# gumstix_expansion_board.net
KiCad netlist of a schematic drawn in Altium Designer
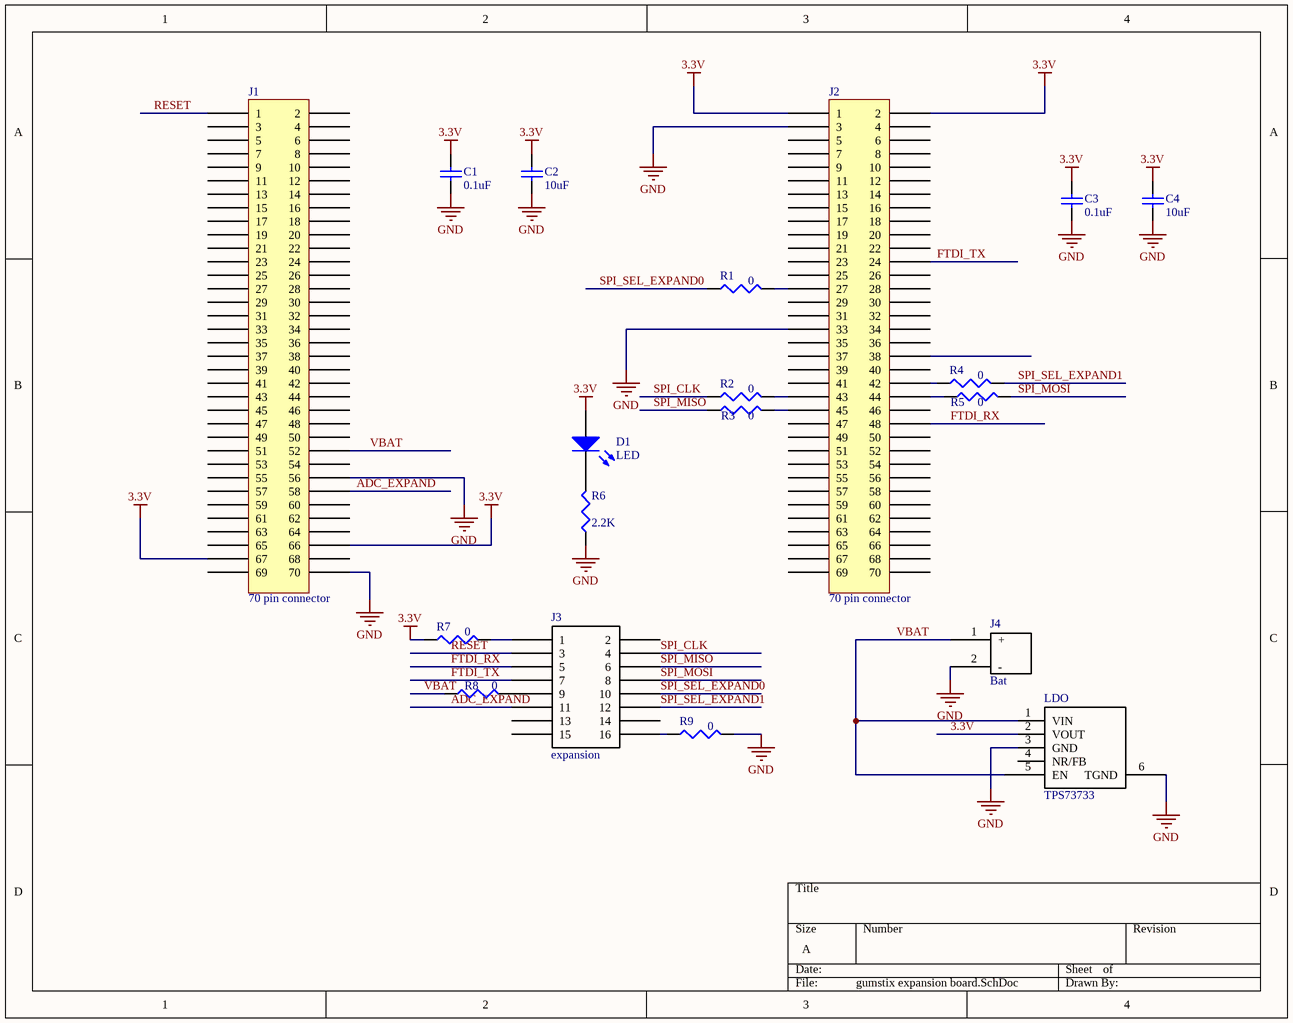
[diagram p0: gumstix expansion board.SchDoc]

(export (version "E")
  (design (tool "Eeschema 10.0.6"))
  (components
    (comp (ref "C1")
      (value "0.1uF")
      (footprint "CAPC1005L")
      (description "Capacitor")
      (fields (field (name "PUBLISHER") "Altium Limited"))
      (libsource (lib "Miscellaneous Devices") (part "Cap"))
    )
    (comp (ref "C2")
      (value "10uF")
      (footprint "CAPC1608L")
      (description "Capacitor (Semiconductor SIM Model)")
      (fields (field (name "Comment") "Cap Semi") (field (name "PUBLISHER") "Altium Limited"))
      (libsource (lib "Miscellaneous Devices") (part "Cap Semi"))
    )
    (comp (ref "C3")
      (value "0.1uF")
      (footprint "CAPC1005L")
      (description "Capacitor")
      (fields (field (name "PUBLISHER") "Altium Limited"))
      (libsource (lib "Miscellaneous Devices") (part "Cap"))
    )
    (comp (ref "C4")
      (value "10uF")
      (footprint "CAPC1608L")
      (description "Capacitor (Semiconductor SIM Model)")
      (fields (field (name "Comment") "Cap Semi") (field (name "PUBLISHER") "Altium Limited"))
      (libsource (lib "Miscellaneous Devices") (part "Cap Semi"))
    )
    (comp (ref "D1") (value "LED") (footprint "SurfaceMount(603)") (libsource (lib "mrone") (part "LED")))
    (comp (ref "J1")
      (value "70 pin connector")
      (footprint "AVX CONN_70")
      (libsource (lib "mrone") (part "70 pin AVX connector"))
    )
    (comp (ref "J2")
      (value "70 pin connector")
      (footprint "AVX CONN_70")
      (libsource (lib "mrone") (part "70 pin AVX connector"))
    )
    (comp (ref "J3")
      (value "expansion")
      (footprint "HEADERSM 8X2")
      (libsource (lib "mrone") (part "HEADER 8X2"))
    )
    (comp (ref "J4")
      (value "Bat")
      (footprint "BatteryConnJST")
      (libsource (lib "mrone") (part "BatteryConnJST"))
    )
    (comp (ref "LDO")
      (value "TPS73733")
      (footprint "SOT-223-5pin")
      (libsource (lib "mrone") (part "LDO33-TI-TPS73733"))
    )
    (comp (ref "R1")
      (value "0")
      (footprint "RESC1608L")
      (description "Resistor")
      (fields (field (name "Comment") "Res3") (field (name "PUBLISHER") "Altium Limited"))
      (libsource (lib "Miscellaneous Devices") (part "Res3"))
    )
    (comp (ref "R2")
      (value "0")
      (footprint "RESC1608L")
      (description "Resistor")
      (fields (field (name "Comment") "Res3") (field (name "PUBLISHER") "Altium Limited"))
      (libsource (lib "Miscellaneous Devices") (part "Res3"))
    )
    (comp (ref "R3")
      (value "0")
      (footprint "RESC1608L")
      (description "Resistor")
      (fields (field (name "Comment") "Res3") (field (name "PUBLISHER") "Altium Limited"))
      (libsource (lib "Miscellaneous Devices") (part "Res3"))
    )
    (comp (ref "R4")
      (value "0")
      (footprint "RESC1608L")
      (description "Resistor")
      (fields (field (name "Comment") "Res3") (field (name "PUBLISHER") "Altium Limited"))
      (libsource (lib "Miscellaneous Devices") (part "Res3"))
    )
    (comp (ref "R5")
      (value "0")
      (footprint "RESC1608L")
      (description "Resistor")
      (fields (field (name "Comment") "Res3") (field (name "PUBLISHER") "Altium Limited"))
      (libsource (lib "Miscellaneous Devices") (part "Res3"))
    )
    (comp (ref "R6")
      (value "2.2K")
      (footprint "RESC1608L")
      (description "Resistor")
      (fields (field (name "Comment") "Res3") (field (name "PUBLISHER") "Altium Limited"))
      (libsource (lib "Miscellaneous Devices") (part "Res3"))
    )
    (comp (ref "R7")
      (value "0")
      (footprint "RESC1608L")
      (description "Resistor")
      (fields (field (name "Comment") "Res3") (field (name "PUBLISHER") "Altium Limited"))
      (libsource (lib "Miscellaneous Devices") (part "Res3"))
    )
    (comp (ref "R8")
      (value "0")
      (footprint "RESC1608L")
      (description "Resistor")
      (fields (field (name "Comment") "Res3") (field (name "PUBLISHER") "Altium Limited"))
      (libsource (lib "Miscellaneous Devices") (part "Res3"))
    )
    (comp (ref "R9")
      (value "0")
      (footprint "RESC1608L")
      (description "Resistor")
      (fields (field (name "Comment") "Res3") (field (name "PUBLISHER") "Altium Limited"))
      (libsource (lib "Miscellaneous Devices") (part "Res3"))
    )
  )
  (nets
    (net (code "1") (name "/ADC_EXPAND") (class "Default")
      (node (ref "J1") (pin "58") (pinfunction "58_58") (pintype "passive"))
      (node (ref "J3") (pin "11") (pinfunction "11_11") (pintype "passive"))
    )
    (net (code "2") (name "/FTDI_RX") (class "Default")
      (node (ref "J2") (pin "48") (pinfunction "48_48") (pintype "passive"))
      (node (ref "J3") (pin "5") (pinfunction "5_5") (pintype "passive"))
    )
    (net (code "3") (name "/FTDI_TX") (class "Default")
      (node (ref "J2") (pin "24") (pinfunction "24_24") (pintype "passive"))
      (node (ref "J3") (pin "7") (pinfunction "7_7") (pintype "passive"))
    )
    (net (code "4") (name "/RESET") (class "Default")
      (node (ref "J1") (pin "1") (pinfunction "1_1") (pintype "passive"))
      (node (ref "J3") (pin "3") (pinfunction "3_3") (pintype "passive"))
    )
    (net (code "5") (name "/SPI_CLK") (class "Default")
      (node (ref "J3") (pin "4") (pinfunction "4_4") (pintype "passive"))
      (node (ref "R2") (pin "1") (pinfunction "1_1") (pintype "passive"))
    )
    (net (code "6") (name "/SPI_MISO") (class "Default")
      (node (ref "J3") (pin "6") (pinfunction "6_6") (pintype "passive"))
      (node (ref "R3") (pin "1") (pinfunction "1_1") (pintype "passive"))
    )
    (net (code "7") (name "/SPI_MOSI") (class "Default")
      (node (ref "J3") (pin "8") (pinfunction "8_8") (pintype "passive"))
      (node (ref "R5") (pin "2") (pinfunction "2_2") (pintype "passive"))
    )
    (net (code "8") (name "/SPI_SEL_EXPAND0") (class "Default")
      (node (ref "J3") (pin "10") (pinfunction "10_10") (pintype "passive"))
      (node (ref "R1") (pin "1") (pinfunction "1_1") (pintype "passive"))
    )
    (net (code "9") (name "/SPI_SEL_EXPAND1") (class "Default")
      (node (ref "J3") (pin "12") (pinfunction "12_12") (pintype "passive"))
      (node (ref "R4") (pin "2") (pinfunction "2_2") (pintype "passive"))
    )
    (net (code "10") (name "/VBAT") (class "Default")
      (node (ref "J1") (pin "52") (pinfunction "52_52") (pintype "passive"))
      (node (ref "J4") (pin "1") (pinfunction "+_1") (pintype "passive"))
      (node (ref "LDO") (pin "1") (pinfunction "VIN_1") (pintype "passive"))
      (node (ref "LDO") (pin "5") (pinfunction "EN_5") (pintype "passive"))
      (node (ref "R8") (pin "1") (pinfunction "1_1") (pintype "passive"))
    )
    (net (code "11") (name "3.3V") (class "Default")
      (node (ref "C1") (pin "2") (pinfunction "2_2") (pintype "passive"))
      (node (ref "C2") (pin "2") (pinfunction "2_2") (pintype "passive"))
      (node (ref "C3") (pin "2") (pinfunction "2_2") (pintype "passive"))
      (node (ref "C4") (pin "2") (pinfunction "2_2") (pintype "passive"))
      (node (ref "D1") (pin "1") (pinfunction "A_1") (pintype "passive"))
      (node (ref "J1") (pin "66") (pinfunction "66_66") (pintype "passive"))
      (node (ref "J1") (pin "67") (pinfunction "67_67") (pintype "passive"))
      (node (ref "J2") (pin "1") (pinfunction "1_1") (pintype "passive"))
      (node (ref "J2") (pin "2") (pinfunction "2_2") (pintype "passive"))
      (node (ref "LDO") (pin "2") (pinfunction "VOUT_2") (pintype "passive"))
      (node (ref "R7") (pin "1") (pinfunction "1_1") (pintype "passive"))
    )
    (net (code "12") (name "GND") (class "Default")
      (node (ref "C1") (pin "1") (pinfunction "1_1") (pintype "passive"))
      (node (ref "C2") (pin "1") (pinfunction "1_1") (pintype "passive"))
      (node (ref "C3") (pin "1") (pinfunction "1_1") (pintype "passive"))
      (node (ref "C4") (pin "1") (pinfunction "1_1") (pintype "passive"))
      (node (ref "J1") (pin "56") (pinfunction "56_56") (pintype "passive"))
      (node (ref "J1") (pin "70") (pinfunction "70_70") (pintype "passive"))
      (node (ref "J2") (pin "3") (pinfunction "3_3") (pintype "passive"))
      (node (ref "J2") (pin "33") (pinfunction "33_33") (pintype "passive"))
      (node (ref "J4") (pin "2") (pinfunction "-_2") (pintype "passive"))
      (node (ref "LDO") (pin "3") (pinfunction "GND_3") (pintype "passive"))
      (node (ref "LDO") (pin "6") (pinfunction "TGND_6") (pintype "passive"))
      (node (ref "R6") (pin "1") (pinfunction "1_1") (pintype "passive"))
      (node (ref "R9") (pin "2") (pinfunction "2_2") (pintype "passive"))
    )
    (net (code "13") (name "Net-(D1-K)") (class "Default")
      (node (ref "D1") (pin "2") (pinfunction "K_2") (pintype "passive"))
      (node (ref "R6") (pin "2") (pinfunction "2_2") (pintype "passive"))
    )
    (net (code "14") (name "Net-(J2-Pad27)") (class "Default")
      (node (ref "J2") (pin "27") (pinfunction "27_27") (pintype "passive"))
      (node (ref "R1") (pin "2") (pinfunction "2_2") (pintype "passive"))
    )
    (net (code "15") (name "Net-(J2-Pad42)") (class "Default")
      (node (ref "J2") (pin "42") (pinfunction "42_42") (pintype "passive"))
      (node (ref "R4") (pin "1") (pinfunction "1_1") (pintype "passive"))
    )
    (net (code "16") (name "Net-(J2-Pad43)") (class "Default")
      (node (ref "J2") (pin "43") (pinfunction "43_43") (pintype "passive"))
      (node (ref "R2") (pin "2") (pinfunction "2_2") (pintype "passive"))
    )
    (net (code "17") (name "Net-(J2-Pad44)") (class "Default")
      (node (ref "J2") (pin "44") (pinfunction "44_44") (pintype "passive"))
      (node (ref "R5") (pin "1") (pinfunction "1_1") (pintype "passive"))
    )
    (net (code "18") (name "Net-(J2-Pad45)") (class "Default")
      (node (ref "J2") (pin "45") (pinfunction "45_45") (pintype "passive"))
      (node (ref "R3") (pin "2") (pinfunction "2_2") (pintype "passive"))
    )
    (net (code "19") (name "Net-(J3-Pad1)") (class "Default")
      (node (ref "J3") (pin "1") (pinfunction "1_1") (pintype "passive"))
      (node (ref "R7") (pin "2") (pinfunction "2_2") (pintype "passive"))
    )
    (net (code "20") (name "Net-(J3-Pad9)") (class "Default")
      (node (ref "J3") (pin "9") (pinfunction "9_9") (pintype "passive"))
      (node (ref "R8") (pin "2") (pinfunction "2_2") (pintype "passive"))
    )
    (net (code "21") (name "Net-(J3-Pad16)") (class "Default")
      (node (ref "J3") (pin "16") (pinfunction "16_16") (pintype "passive"))
      (node (ref "R9") (pin "1") (pinfunction "1_1") (pintype "passive"))
    )
    (net (code "22") (name "unconnected-(J1-Pad2)") (class "Default")
      (node (ref "J1") (pin "2") (pinfunction "2_2") (pintype "passive"))
    )
    (net (code "23") (name "unconnected-(J1-Pad3)") (class "Default")
      (node (ref "J1") (pin "3") (pinfunction "3_3") (pintype "passive"))
    )
    (net (code "24") (name "unconnected-(J1-Pad4)") (class "Default")
      (node (ref "J1") (pin "4") (pinfunction "4_4") (pintype "passive"))
    )
    (net (code "25") (name "unconnected-(J1-Pad5)") (class "Default")
      (node (ref "J1") (pin "5") (pinfunction "5_5") (pintype "passive"))
    )
    (net (code "26") (name "unconnected-(J1-Pad6)") (class "Default")
      (node (ref "J1") (pin "6") (pinfunction "6_6") (pintype "passive"))
    )
    (net (code "27") (name "unconnected-(J1-Pad7)") (class "Default")
      (node (ref "J1") (pin "7") (pinfunction "7_7") (pintype "passive"))
    )
    (net (code "28") (name "unconnected-(J1-Pad8)") (class "Default")
      (node (ref "J1") (pin "8") (pinfunction "8_8") (pintype "passive"))
    )
    (net (code "29") (name "unconnected-(J1-Pad9)") (class "Default")
      (node (ref "J1") (pin "9") (pinfunction "9_9") (pintype "passive"))
    )
    (net (code "30") (name "unconnected-(J1-Pad10)") (class "Default")
      (node (ref "J1") (pin "10") (pinfunction "10_10") (pintype "passive"))
    )
    (net (code "31") (name "unconnected-(J1-Pad11)") (class "Default")
      (node (ref "J1") (pin "11") (pinfunction "11_11") (pintype "passive"))
    )
    (net (code "32") (name "unconnected-(J1-Pad12)") (class "Default")
      (node (ref "J1") (pin "12") (pinfunction "12_12") (pintype "passive"))
    )
    (net (code "33") (name "unconnected-(J1-Pad13)") (class "Default")
      (node (ref "J1") (pin "13") (pinfunction "13_13") (pintype "passive"))
    )
    (net (code "34") (name "unconnected-(J1-Pad14)") (class "Default")
      (node (ref "J1") (pin "14") (pinfunction "14_14") (pintype "passive"))
    )
    (net (code "35") (name "unconnected-(J1-Pad15)") (class "Default")
      (node (ref "J1") (pin "15") (pinfunction "15_15") (pintype "passive"))
    )
    (net (code "36") (name "unconnected-(J1-Pad16)") (class "Default")
      (node (ref "J1") (pin "16") (pinfunction "16_16") (pintype "passive"))
    )
    (net (code "37") (name "unconnected-(J1-Pad17)") (class "Default")
      (node (ref "J1") (pin "17") (pinfunction "17_17") (pintype "passive"))
    )
    (net (code "38") (name "unconnected-(J1-Pad18)") (class "Default")
      (node (ref "J1") (pin "18") (pinfunction "18_18") (pintype "passive"))
    )
    (net (code "39") (name "unconnected-(J1-Pad19)") (class "Default")
      (node (ref "J1") (pin "19") (pinfunction "19_19") (pintype "passive"))
    )
    (net (code "40") (name "unconnected-(J1-Pad20)") (class "Default")
      (node (ref "J1") (pin "20") (pinfunction "20_20") (pintype "passive"))
    )
    (net (code "41") (name "unconnected-(J1-Pad21)") (class "Default")
      (node (ref "J1") (pin "21") (pinfunction "21_21") (pintype "passive"))
    )
    (net (code "42") (name "unconnected-(J1-Pad22)") (class "Default")
      (node (ref "J1") (pin "22") (pinfunction "22_22") (pintype "passive"))
    )
    (net (code "43") (name "unconnected-(J1-Pad23)") (class "Default")
      (node (ref "J1") (pin "23") (pinfunction "23_23") (pintype "passive"))
    )
    (net (code "44") (name "unconnected-(J1-Pad24)") (class "Default")
      (node (ref "J1") (pin "24") (pinfunction "24_24") (pintype "passive"))
    )
    (net (code "45") (name "unconnected-(J1-Pad25)") (class "Default")
      (node (ref "J1") (pin "25") (pinfunction "25_25") (pintype "passive"))
    )
    (net (code "46") (name "unconnected-(J1-Pad26)") (class "Default")
      (node (ref "J1") (pin "26") (pinfunction "26_26") (pintype "passive"))
    )
    (net (code "47") (name "unconnected-(J1-Pad27)") (class "Default")
      (node (ref "J1") (pin "27") (pinfunction "27_27") (pintype "passive"))
    )
    (net (code "48") (name "unconnected-(J1-Pad28)") (class "Default")
      (node (ref "J1") (pin "28") (pinfunction "28_28") (pintype "passive"))
    )
    (net (code "49") (name "unconnected-(J1-Pad29)") (class "Default")
      (node (ref "J1") (pin "29") (pinfunction "29_29") (pintype "passive"))
    )
    (net (code "50") (name "unconnected-(J1-Pad30)") (class "Default")
      (node (ref "J1") (pin "30") (pinfunction "30_30") (pintype "passive"))
    )
    (net (code "51") (name "unconnected-(J1-Pad31)") (class "Default")
      (node (ref "J1") (pin "31") (pinfunction "31_31") (pintype "passive"))
    )
    (net (code "52") (name "unconnected-(J1-Pad32)") (class "Default")
      (node (ref "J1") (pin "32") (pinfunction "32_32") (pintype "passive"))
    )
    (net (code "53") (name "unconnected-(J1-Pad33)") (class "Default")
      (node (ref "J1") (pin "33") (pinfunction "33_33") (pintype "passive"))
    )
    (net (code "54") (name "unconnected-(J1-Pad34)") (class "Default")
      (node (ref "J1") (pin "34") (pinfunction "34_34") (pintype "passive"))
    )
    (net (code "55") (name "unconnected-(J1-Pad35)") (class "Default")
      (node (ref "J1") (pin "35") (pinfunction "35_35") (pintype "passive"))
    )
    (net (code "56") (name "unconnected-(J1-Pad36)") (class "Default")
      (node (ref "J1") (pin "36") (pinfunction "36_36") (pintype "passive"))
    )
    (net (code "57") (name "unconnected-(J1-Pad37)") (class "Default")
      (node (ref "J1") (pin "37") (pinfunction "37_37") (pintype "passive"))
    )
    (net (code "58") (name "unconnected-(J1-Pad38)") (class "Default")
      (node (ref "J1") (pin "38") (pinfunction "38_38") (pintype "passive"))
    )
    (net (code "59") (name "unconnected-(J1-Pad39)") (class "Default")
      (node (ref "J1") (pin "39") (pinfunction "39_39") (pintype "passive"))
    )
    (net (code "60") (name "unconnected-(J1-Pad40)") (class "Default")
      (node (ref "J1") (pin "40") (pinfunction "40_40") (pintype "passive"))
    )
    (net (code "61") (name "unconnected-(J1-Pad41)") (class "Default")
      (node (ref "J1") (pin "41") (pinfunction "41_41") (pintype "passive"))
    )
    (net (code "62") (name "unconnected-(J1-Pad42)") (class "Default")
      (node (ref "J1") (pin "42") (pinfunction "42_42") (pintype "passive"))
    )
    (net (code "63") (name "unconnected-(J1-Pad43)") (class "Default")
      (node (ref "J1") (pin "43") (pinfunction "43_43") (pintype "passive"))
    )
    (net (code "64") (name "unconnected-(J1-Pad44)") (class "Default")
      (node (ref "J1") (pin "44") (pinfunction "44_44") (pintype "passive"))
    )
    (net (code "65") (name "unconnected-(J1-Pad45)") (class "Default")
      (node (ref "J1") (pin "45") (pinfunction "45_45") (pintype "passive"))
    )
    (net (code "66") (name "unconnected-(J1-Pad46)") (class "Default")
      (node (ref "J1") (pin "46") (pinfunction "46_46") (pintype "passive"))
    )
    (net (code "67") (name "unconnected-(J1-Pad47)") (class "Default")
      (node (ref "J1") (pin "47") (pinfunction "47_47") (pintype "passive"))
    )
    (net (code "68") (name "unconnected-(J1-Pad48)") (class "Default")
      (node (ref "J1") (pin "48") (pinfunction "48_48") (pintype "passive"))
    )
    (net (code "69") (name "unconnected-(J1-Pad49)") (class "Default")
      (node (ref "J1") (pin "49") (pinfunction "49_49") (pintype "passive"))
    )
    (net (code "70") (name "unconnected-(J1-Pad50)") (class "Default")
      (node (ref "J1") (pin "50") (pinfunction "50_50") (pintype "passive"))
    )
    (net (code "71") (name "unconnected-(J1-Pad51)") (class "Default")
      (node (ref "J1") (pin "51") (pinfunction "51_51") (pintype "passive"))
    )
    (net (code "72") (name "unconnected-(J1-Pad53)") (class "Default")
      (node (ref "J1") (pin "53") (pinfunction "53_53") (pintype "passive"))
    )
    (net (code "73") (name "unconnected-(J1-Pad54)") (class "Default")
      (node (ref "J1") (pin "54") (pinfunction "54_54") (pintype "passive"))
    )
    (net (code "74") (name "unconnected-(J1-Pad55)") (class "Default")
      (node (ref "J1") (pin "55") (pinfunction "55_55") (pintype "passive"))
    )
    (net (code "75") (name "unconnected-(J1-Pad57)") (class "Default")
      (node (ref "J1") (pin "57") (pinfunction "57_57") (pintype "passive"))
    )
    (net (code "76") (name "unconnected-(J1-Pad59)") (class "Default")
      (node (ref "J1") (pin "59") (pinfunction "59_59") (pintype "passive"))
    )
    (net (code "77") (name "unconnected-(J1-Pad60)") (class "Default")
      (node (ref "J1") (pin "60") (pinfunction "60_60") (pintype "passive"))
    )
    (net (code "78") (name "unconnected-(J1-Pad61)") (class "Default")
      (node (ref "J1") (pin "61") (pinfunction "61_61") (pintype "passive"))
    )
    (net (code "79") (name "unconnected-(J1-Pad62)") (class "Default")
      (node (ref "J1") (pin "62") (pinfunction "62_62") (pintype "passive"))
    )
    (net (code "80") (name "unconnected-(J1-Pad63)") (class "Default")
      (node (ref "J1") (pin "63") (pinfunction "63_63") (pintype "passive"))
    )
    (net (code "81") (name "unconnected-(J1-Pad64)") (class "Default")
      (node (ref "J1") (pin "64") (pinfunction "64_64") (pintype "passive"))
    )
    (net (code "82") (name "unconnected-(J1-Pad65)") (class "Default")
      (node (ref "J1") (pin "65") (pinfunction "65_65") (pintype "passive"))
    )
    (net (code "83") (name "unconnected-(J1-Pad68)") (class "Default")
      (node (ref "J1") (pin "68") (pinfunction "68_68") (pintype "passive"))
    )
    (net (code "84") (name "unconnected-(J1-Pad69)") (class "Default")
      (node (ref "J1") (pin "69") (pinfunction "69_69") (pintype "passive"))
    )
    (net (code "85") (name "unconnected-(J2-Pad4)") (class "Default")
      (node (ref "J2") (pin "4") (pinfunction "4_4") (pintype "passive"))
    )
    (net (code "86") (name "unconnected-(J2-Pad5)") (class "Default")
      (node (ref "J2") (pin "5") (pinfunction "5_5") (pintype "passive"))
    )
    (net (code "87") (name "unconnected-(J2-Pad6)") (class "Default")
      (node (ref "J2") (pin "6") (pinfunction "6_6") (pintype "passive"))
    )
    (net (code "88") (name "unconnected-(J2-Pad7)") (class "Default")
      (node (ref "J2") (pin "7") (pinfunction "7_7") (pintype "passive"))
    )
    (net (code "89") (name "unconnected-(J2-Pad8)") (class "Default")
      (node (ref "J2") (pin "8") (pinfunction "8_8") (pintype "passive"))
    )
    (net (code "90") (name "unconnected-(J2-Pad9)") (class "Default")
      (node (ref "J2") (pin "9") (pinfunction "9_9") (pintype "passive"))
    )
    (net (code "91") (name "unconnected-(J2-Pad10)") (class "Default")
      (node (ref "J2") (pin "10") (pinfunction "10_10") (pintype "passive"))
    )
    (net (code "92") (name "unconnected-(J2-Pad11)") (class "Default")
      (node (ref "J2") (pin "11") (pinfunction "11_11") (pintype "passive"))
    )
    (net (code "93") (name "unconnected-(J2-Pad12)") (class "Default")
      (node (ref "J2") (pin "12") (pinfunction "12_12") (pintype "passive"))
    )
    (net (code "94") (name "unconnected-(J2-Pad13)") (class "Default")
      (node (ref "J2") (pin "13") (pinfunction "13_13") (pintype "passive"))
    )
    (net (code "95") (name "unconnected-(J2-Pad14)") (class "Default")
      (node (ref "J2") (pin "14") (pinfunction "14_14") (pintype "passive"))
    )
    (net (code "96") (name "unconnected-(J2-Pad15)") (class "Default")
      (node (ref "J2") (pin "15") (pinfunction "15_15") (pintype "passive"))
    )
    (net (code "97") (name "unconnected-(J2-Pad16)") (class "Default")
      (node (ref "J2") (pin "16") (pinfunction "16_16") (pintype "passive"))
    )
    (net (code "98") (name "unconnected-(J2-Pad17)") (class "Default")
      (node (ref "J2") (pin "17") (pinfunction "17_17") (pintype "passive"))
    )
    (net (code "99") (name "unconnected-(J2-Pad18)") (class "Default")
      (node (ref "J2") (pin "18") (pinfunction "18_18") (pintype "passive"))
    )
    (net (code "100") (name "unconnected-(J2-Pad19)") (class "Default")
      (node (ref "J2") (pin "19") (pinfunction "19_19") (pintype "passive"))
    )
    (net (code "101") (name "unconnected-(J2-Pad20)") (class "Default")
      (node (ref "J2") (pin "20") (pinfunction "20_20") (pintype "passive"))
    )
    (net (code "102") (name "unconnected-(J2-Pad21)") (class "Default")
      (node (ref "J2") (pin "21") (pinfunction "21_21") (pintype "passive"))
    )
    (net (code "103") (name "unconnected-(J2-Pad22)") (class "Default")
      (node (ref "J2") (pin "22") (pinfunction "22_22") (pintype "passive"))
    )
    (net (code "104") (name "unconnected-(J2-Pad23)") (class "Default")
      (node (ref "J2") (pin "23") (pinfunction "23_23") (pintype "passive"))
    )
    (net (code "105") (name "unconnected-(J2-Pad25)") (class "Default")
      (node (ref "J2") (pin "25") (pinfunction "25_25") (pintype "passive"))
    )
    (net (code "106") (name "unconnected-(J2-Pad26)") (class "Default")
      (node (ref "J2") (pin "26") (pinfunction "26_26") (pintype "passive"))
    )
    (net (code "107") (name "unconnected-(J2-Pad28)") (class "Default")
      (node (ref "J2") (pin "28") (pinfunction "28_28") (pintype "passive"))
    )
    (net (code "108") (name "unconnected-(J2-Pad29)") (class "Default")
      (node (ref "J2") (pin "29") (pinfunction "29_29") (pintype "passive"))
    )
    (net (code "109") (name "unconnected-(J2-Pad30)") (class "Default")
      (node (ref "J2") (pin "30") (pinfunction "30_30") (pintype "passive"))
    )
    (net (code "110") (name "unconnected-(J2-Pad31)") (class "Default")
      (node (ref "J2") (pin "31") (pinfunction "31_31") (pintype "passive"))
    )
    (net (code "111") (name "unconnected-(J2-Pad32)") (class "Default")
      (node (ref "J2") (pin "32") (pinfunction "32_32") (pintype "passive"))
    )
    (net (code "112") (name "unconnected-(J2-Pad34)") (class "Default")
      (node (ref "J2") (pin "34") (pinfunction "34_34") (pintype "passive"))
    )
    (net (code "113") (name "unconnected-(J2-Pad35)") (class "Default")
      (node (ref "J2") (pin "35") (pinfunction "35_35") (pintype "passive"))
    )
    (net (code "114") (name "unconnected-(J2-Pad36)") (class "Default")
      (node (ref "J2") (pin "36") (pinfunction "36_36") (pintype "passive"))
    )
    (net (code "115") (name "unconnected-(J2-Pad37)") (class "Default")
      (node (ref "J2") (pin "37") (pinfunction "37_37") (pintype "passive"))
    )
    (net (code "116") (name "unconnected-(J2-Pad38)") (class "Default")
      (node (ref "J2") (pin "38") (pinfunction "38_38") (pintype "passive"))
    )
    (net (code "117") (name "unconnected-(J2-Pad39)") (class "Default")
      (node (ref "J2") (pin "39") (pinfunction "39_39") (pintype "passive"))
    )
    (net (code "118") (name "unconnected-(J2-Pad40)") (class "Default")
      (node (ref "J2") (pin "40") (pinfunction "40_40") (pintype "passive"))
    )
    (net (code "119") (name "unconnected-(J2-Pad41)") (class "Default")
      (node (ref "J2") (pin "41") (pinfunction "41_41") (pintype "passive"))
    )
    (net (code "120") (name "unconnected-(J2-Pad46)") (class "Default")
      (node (ref "J2") (pin "46") (pinfunction "46_46") (pintype "passive"))
    )
    (net (code "121") (name "unconnected-(J2-Pad47)") (class "Default")
      (node (ref "J2") (pin "47") (pinfunction "47_47") (pintype "passive"))
    )
    (net (code "122") (name "unconnected-(J2-Pad49)") (class "Default")
      (node (ref "J2") (pin "49") (pinfunction "49_49") (pintype "passive"))
    )
    (net (code "123") (name "unconnected-(J2-Pad50)") (class "Default")
      (node (ref "J2") (pin "50") (pinfunction "50_50") (pintype "passive"))
    )
    (net (code "124") (name "unconnected-(J2-Pad51)") (class "Default")
      (node (ref "J2") (pin "51") (pinfunction "51_51") (pintype "passive"))
    )
    (net (code "125") (name "unconnected-(J2-Pad52)") (class "Default")
      (node (ref "J2") (pin "52") (pinfunction "52_52") (pintype "passive"))
    )
    (net (code "126") (name "unconnected-(J2-Pad53)") (class "Default")
      (node (ref "J2") (pin "53") (pinfunction "53_53") (pintype "passive"))
    )
    (net (code "127") (name "unconnected-(J2-Pad54)") (class "Default")
      (node (ref "J2") (pin "54") (pinfunction "54_54") (pintype "passive"))
    )
    (net (code "128") (name "unconnected-(J2-Pad55)") (class "Default")
      (node (ref "J2") (pin "55") (pinfunction "55_55") (pintype "passive"))
    )
    (net (code "129") (name "unconnected-(J2-Pad56)") (class "Default")
      (node (ref "J2") (pin "56") (pinfunction "56_56") (pintype "passive"))
    )
    (net (code "130") (name "unconnected-(J2-Pad57)") (class "Default")
      (node (ref "J2") (pin "57") (pinfunction "57_57") (pintype "passive"))
    )
    (net (code "131") (name "unconnected-(J2-Pad58)") (class "Default")
      (node (ref "J2") (pin "58") (pinfunction "58_58") (pintype "passive"))
    )
    (net (code "132") (name "unconnected-(J2-Pad59)") (class "Default")
      (node (ref "J2") (pin "59") (pinfunction "59_59") (pintype "passive"))
    )
    (net (code "133") (name "unconnected-(J2-Pad60)") (class "Default")
      (node (ref "J2") (pin "60") (pinfunction "60_60") (pintype "passive"))
    )
    (net (code "134") (name "unconnected-(J2-Pad61)") (class "Default")
      (node (ref "J2") (pin "61") (pinfunction "61_61") (pintype "passive"))
    )
    (net (code "135") (name "unconnected-(J2-Pad62)") (class "Default")
      (node (ref "J2") (pin "62") (pinfunction "62_62") (pintype "passive"))
    )
    (net (code "136") (name "unconnected-(J2-Pad63)") (class "Default")
      (node (ref "J2") (pin "63") (pinfunction "63_63") (pintype "passive"))
    )
    (net (code "137") (name "unconnected-(J2-Pad64)") (class "Default")
      (node (ref "J2") (pin "64") (pinfunction "64_64") (pintype "passive"))
    )
    (net (code "138") (name "unconnected-(J2-Pad65)") (class "Default")
      (node (ref "J2") (pin "65") (pinfunction "65_65") (pintype "passive"))
    )
    (net (code "139") (name "unconnected-(J2-Pad66)") (class "Default")
      (node (ref "J2") (pin "66") (pinfunction "66_66") (pintype "passive"))
    )
    (net (code "140") (name "unconnected-(J2-Pad67)") (class "Default")
      (node (ref "J2") (pin "67") (pinfunction "67_67") (pintype "passive"))
    )
    (net (code "141") (name "unconnected-(J2-Pad68)") (class "Default")
      (node (ref "J2") (pin "68") (pinfunction "68_68") (pintype "passive"))
    )
    (net (code "142") (name "unconnected-(J2-Pad69)") (class "Default")
      (node (ref "J2") (pin "69") (pinfunction "69_69") (pintype "passive"))
    )
    (net (code "143") (name "unconnected-(J2-Pad70)") (class "Default")
      (node (ref "J2") (pin "70") (pinfunction "70_70") (pintype "passive"))
    )
    (net (code "144") (name "unconnected-(J3-Pad2)") (class "Default")
      (node (ref "J3") (pin "2") (pinfunction "2_2") (pintype "passive"))
    )
    (net (code "145") (name "unconnected-(J3-Pad13)") (class "Default")
      (node (ref "J3") (pin "13") (pinfunction "13_13") (pintype "passive"))
    )
    (net (code "146") (name "unconnected-(J3-Pad14)") (class "Default")
      (node (ref "J3") (pin "14") (pinfunction "14_14") (pintype "passive"))
    )
    (net (code "147") (name "unconnected-(J3-Pad15)") (class "Default")
      (node (ref "J3") (pin "15") (pinfunction "15_15") (pintype "passive"))
    )
    (net (code "148") (name "unconnected-(LDO-NR{slash}FB-Pad4)") (class "Default")
      (node (ref "LDO") (pin "4") (pinfunction "NR/FB_4") (pintype "passive"))
    )
  )
)
